# L1Demoscene_v2.net
KiCad netlist of a schematic drawn in EAGLE
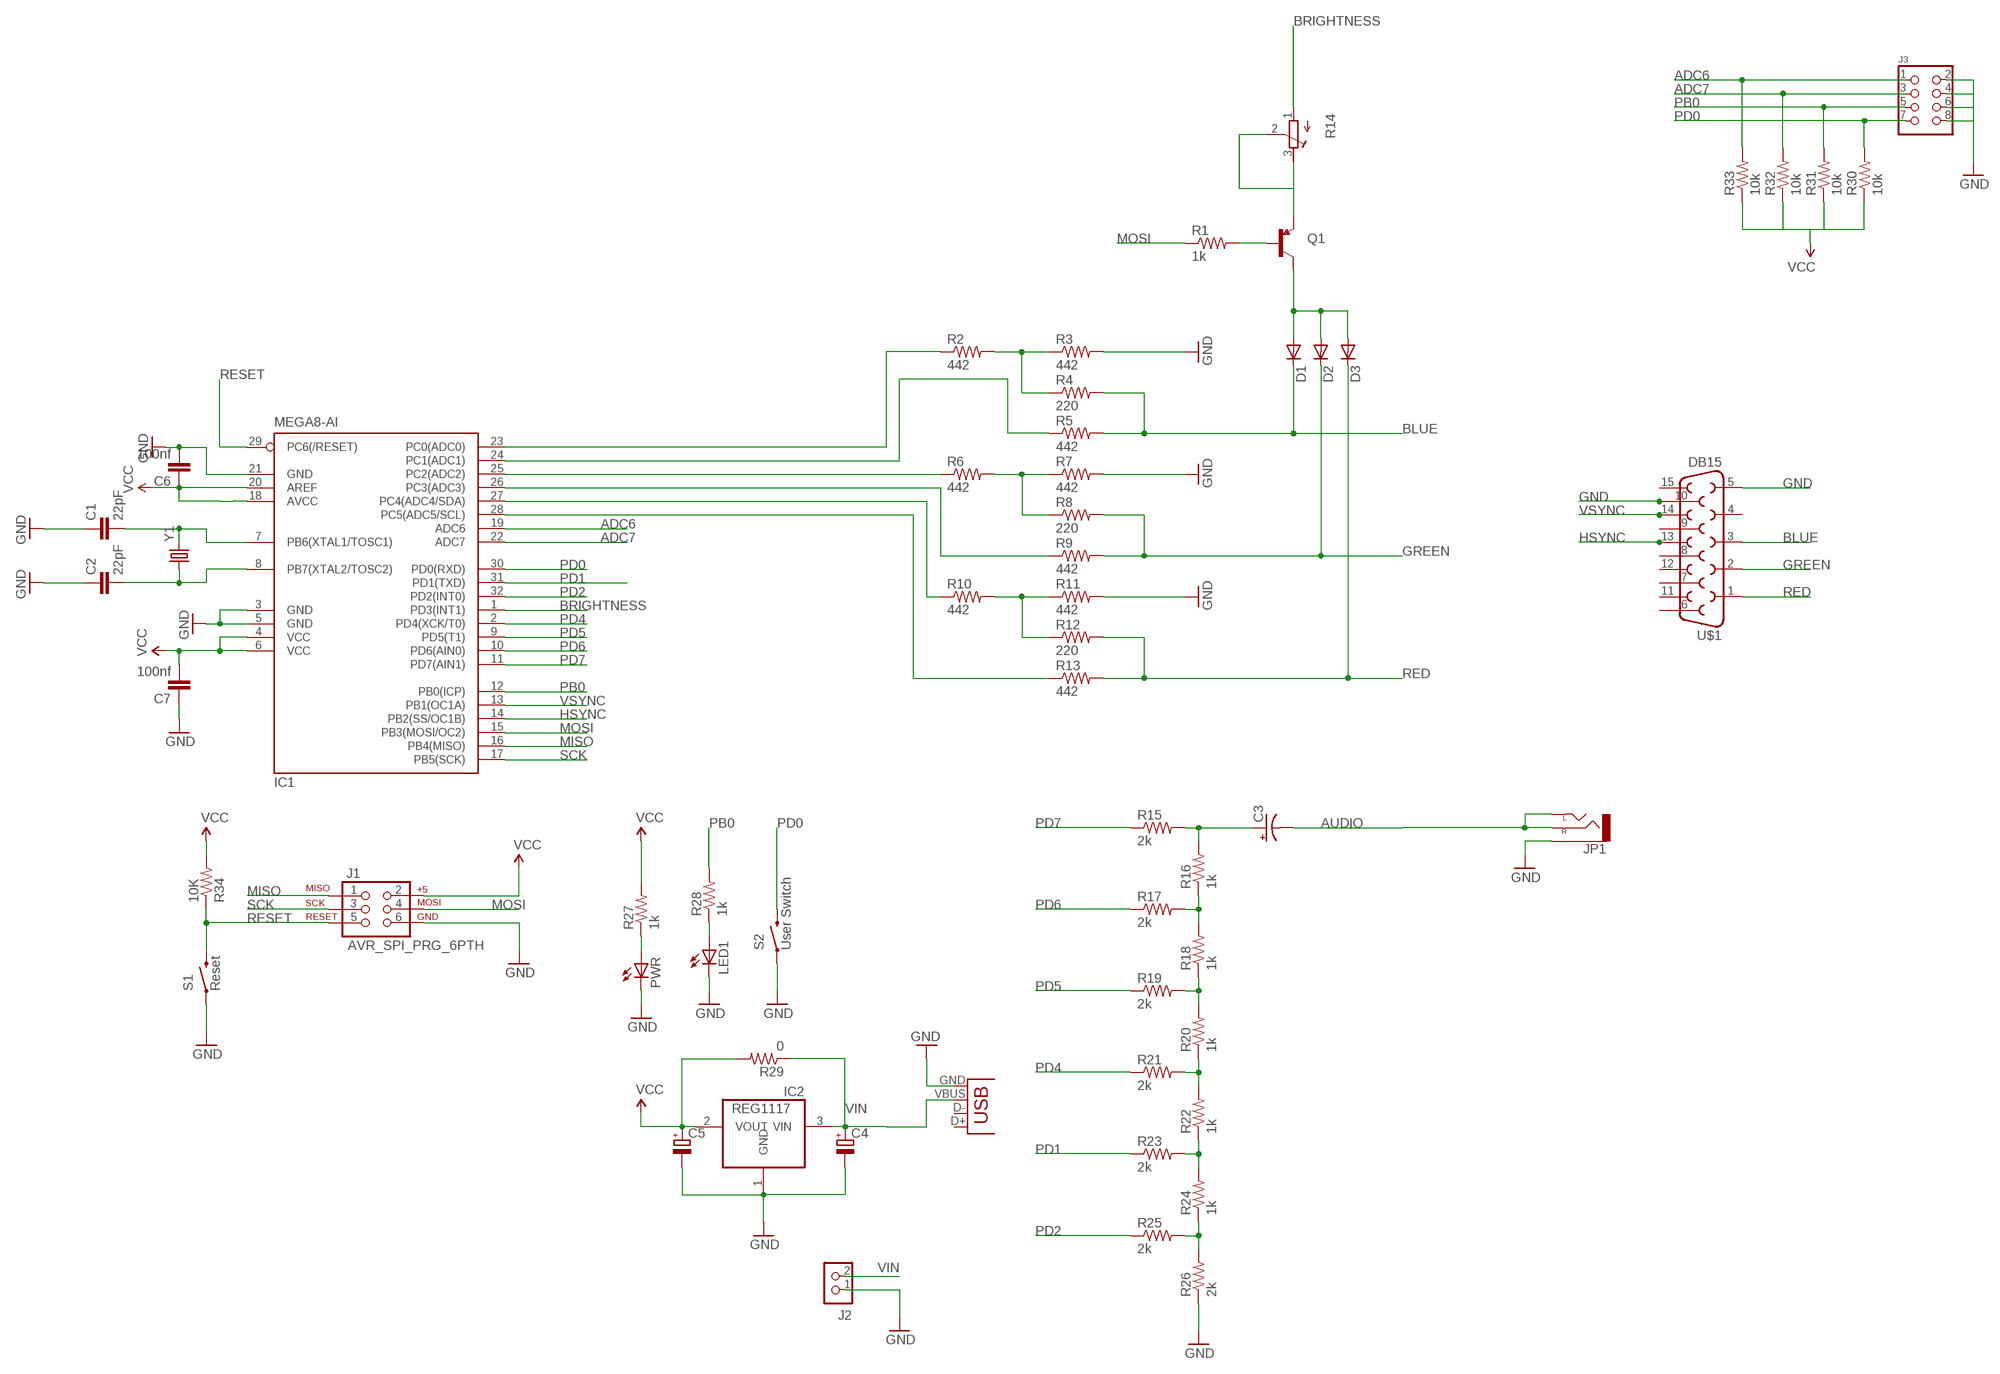
[diagram p0: schematic, sheet 1]

(export (version "E")
  (design (tool "Eeschema 10.0.6"))
  (components
    (comp (ref "10K")
      (value "R34")
      (footprint "eagle-import:0603-RES")
      (libsource (lib "eagle-import") (part "RESISTOR0603-RES"))
    )
    (comp (ref "C1")
      (value "22pF")
      (footprint "eagle-import:0603-CAP")
      (libsource (lib "eagle-import") (part "CAP0603-CAP"))
    )
    (comp (ref "C2")
      (value "22pF")
      (footprint "eagle-import:0603-CAP")
      (libsource (lib "eagle-import") (part "CAP0603-CAP"))
    )
    (comp (ref "C3")
      (value "CAP_POL1206")
      (footprint "eagle-import:EIA3216")
      (libsource (lib "eagle-import") (part "CAP_POL1206"))
    )
    (comp (ref "C4")
      (value "CAPACITOR_POL-SMC_A")
      (footprint "eagle-import:SMC_A")
      (libsource (lib "eagle-import") (part "CAPACITOR_POL-SMC_A"))
    )
    (comp (ref "C5")
      (value "CAPACITOR_POL-SMC_A")
      (footprint "eagle-import:SMC_A")
      (libsource (lib "eagle-import") (part "CAPACITOR_POL-SMC_A"))
    )
    (comp (ref "C6")
      (value "100nf")
      (footprint "eagle-import:0603-CAP")
      (libsource (lib "eagle-import") (part "CAP0603-CAP"))
    )
    (comp (ref "C7")
      (value "100nf")
      (footprint "eagle-import:0603-CAP")
      (libsource (lib "eagle-import") (part "CAP0603-CAP"))
    )
    (comp (ref "D1")
      (value "DIODESOD")
      (footprint "eagle-import:SOD-323")
      (libsource (lib "eagle-import") (part "DIODESOD"))
    )
    (comp (ref "D2")
      (value "DIODESOD")
      (footprint "eagle-import:SOD-323")
      (libsource (lib "eagle-import") (part "DIODESOD"))
    )
    (comp (ref "D3")
      (value "DIODESOD")
      (footprint "eagle-import:SOD-323")
      (libsource (lib "eagle-import") (part "DIODESOD"))
    )
    (comp (ref "IC1")
      (value "MEGA8-AI")
      (footprint "eagle-import:TQFP32-08")
      (fields (field (name "MPN") "ATMEGA8-16AU"))
      (libsource (lib "eagle-import") (part "MEGA8-AI"))
    )
    (comp (ref "IC2")
      (value "REG1117")
      (footprint "eagle-import:SOT223")
      (libsource (lib "eagle-import") (part "REG1117"))
    )
    (comp (ref "J1")
      (value "AVR_SPI_PRG_6PTH")
      (footprint "eagle-import:2X3")
      (libsource (lib "eagle-import") (part "AVR_SPI_PRG_6PTH"))
    )
    (comp (ref "J2")
      (value "CON_HEADER_1X02-PTH")
      (footprint "eagle-import:M1X2")
      (libsource (lib "eagle-import") (part "CON_HEADER_1X02-PTH"))
    )
    (comp (ref "J3")
      (value "CON_HEADER_2X04-PTH")
      (footprint "eagle-import:M2X4")
      (libsource (lib "eagle-import") (part "CON_HEADER_2X04-PTH"))
    )
    (comp (ref "JP1")
      (value "AUDIO-JACKPTH")
      (footprint "eagle-import:AUDIO-JACK")
      (libsource (lib "eagle-import") (part "AUDIO-JACKPTH"))
    )
    (comp (ref "LED1")
      (value "LED-0603")
      (footprint "eagle-import:LED-603")
      (libsource (lib "eagle-import") (part "LED-0603"))
    )
    (comp (ref "PWR")
      (value "LED-0603")
      (footprint "eagle-import:LED-603")
      (libsource (lib "eagle-import") (part "LED-0603"))
    )
    (comp (ref "Q1")
      (value "TRANSISTOR_PNPSMD")
      (footprint "eagle-import:SOT23-3")
      (libsource (lib "eagle-import") (part "TRANSISTOR_PNPSMD"))
    )
    (comp (ref "R1")
      (value "1k")
      (footprint "eagle-import:0603-RES")
      (libsource (lib "eagle-import") (part "RESISTOR0603-RES"))
    )
    (comp (ref "R2")
      (value "442")
      (footprint "eagle-import:0603-RES")
      (libsource (lib "eagle-import") (part "RESISTOR0603-RES"))
    )
    (comp (ref "R3")
      (value "442")
      (footprint "eagle-import:0603-RES")
      (libsource (lib "eagle-import") (part "RESISTOR0603-RES"))
    )
    (comp (ref "R4")
      (value "220")
      (footprint "eagle-import:0603-RES")
      (libsource (lib "eagle-import") (part "RESISTOR0603-RES"))
    )
    (comp (ref "R5")
      (value "442")
      (footprint "eagle-import:0603-RES")
      (libsource (lib "eagle-import") (part "RESISTOR0603-RES"))
    )
    (comp (ref "R6")
      (value "442")
      (footprint "eagle-import:0603-RES")
      (libsource (lib "eagle-import") (part "RESISTOR0603-RES"))
    )
    (comp (ref "R7")
      (value "442")
      (footprint "eagle-import:0603-RES")
      (libsource (lib "eagle-import") (part "RESISTOR0603-RES"))
    )
    (comp (ref "R8")
      (value "220")
      (footprint "eagle-import:0603-RES")
      (libsource (lib "eagle-import") (part "RESISTOR0603-RES"))
    )
    (comp (ref "R9")
      (value "442")
      (footprint "eagle-import:0603-RES")
      (libsource (lib "eagle-import") (part "RESISTOR0603-RES"))
    )
    (comp (ref "R10")
      (value "442")
      (footprint "eagle-import:0603-RES")
      (libsource (lib "eagle-import") (part "RESISTOR0603-RES"))
    )
    (comp (ref "R11")
      (value "442")
      (footprint "eagle-import:0603-RES")
      (libsource (lib "eagle-import") (part "RESISTOR0603-RES"))
    )
    (comp (ref "R12")
      (value "220")
      (footprint "eagle-import:0603-RES")
      (libsource (lib "eagle-import") (part "RESISTOR0603-RES"))
    )
    (comp (ref "R13")
      (value "442")
      (footprint "eagle-import:0603-RES")
      (libsource (lib "eagle-import") (part "RESISTOR0603-RES"))
    )
    (comp (ref "R14")
      (value "R-TRIMM3296W")
      (footprint "eagle-import:RTRIM3296W")
      (libsource (lib "eagle-import") (part "R-TRIMM3296W"))
    )
    (comp (ref "R15")
      (value "2k")
      (footprint "eagle-import:0603-RES")
      (libsource (lib "eagle-import") (part "RESISTOR0603-RES"))
    )
    (comp (ref "R16")
      (value "1k")
      (footprint "eagle-import:0603-RES")
      (libsource (lib "eagle-import") (part "RESISTOR0603-RES"))
    )
    (comp (ref "R17")
      (value "2k")
      (footprint "eagle-import:0603-RES")
      (libsource (lib "eagle-import") (part "RESISTOR0603-RES"))
    )
    (comp (ref "R18")
      (value "1k")
      (footprint "eagle-import:0603-RES")
      (libsource (lib "eagle-import") (part "RESISTOR0603-RES"))
    )
    (comp (ref "R19")
      (value "2k")
      (footprint "eagle-import:0603-RES")
      (libsource (lib "eagle-import") (part "RESISTOR0603-RES"))
    )
    (comp (ref "R20")
      (value "1k")
      (footprint "eagle-import:0603-RES")
      (libsource (lib "eagle-import") (part "RESISTOR0603-RES"))
    )
    (comp (ref "R21")
      (value "2k")
      (footprint "eagle-import:0603-RES")
      (libsource (lib "eagle-import") (part "RESISTOR0603-RES"))
    )
    (comp (ref "R22")
      (value "1k")
      (footprint "eagle-import:0603-RES")
      (libsource (lib "eagle-import") (part "RESISTOR0603-RES"))
    )
    (comp (ref "R23")
      (value "2k")
      (footprint "eagle-import:0603-RES")
      (libsource (lib "eagle-import") (part "RESISTOR0603-RES"))
    )
    (comp (ref "R24")
      (value "1k")
      (footprint "eagle-import:0603-RES")
      (libsource (lib "eagle-import") (part "RESISTOR0603-RES"))
    )
    (comp (ref "R25")
      (value "2k")
      (footprint "eagle-import:0603-RES")
      (libsource (lib "eagle-import") (part "RESISTOR0603-RES"))
    )
    (comp (ref "R26")
      (value "2k")
      (footprint "eagle-import:0603-RES")
      (libsource (lib "eagle-import") (part "RESISTOR0603-RES"))
    )
    (comp (ref "R27")
      (value "1k")
      (footprint "eagle-import:0603-RES")
      (libsource (lib "eagle-import") (part "RESISTOR0603-RES"))
    )
    (comp (ref "R28")
      (value "1k")
      (footprint "eagle-import:0603-RES")
      (libsource (lib "eagle-import") (part "RESISTOR0603-RES"))
    )
    (comp (ref "R29")
      (value "0")
      (footprint "eagle-import:1206")
      (libsource (lib "eagle-import") (part "RESISTOR1206"))
    )
    (comp (ref "R30")
      (value "10k")
      (footprint "eagle-import:0603-RES")
      (libsource (lib "eagle-import") (part "RESISTOR0603-RES"))
    )
    (comp (ref "R31")
      (value "10k")
      (footprint "eagle-import:0603-RES")
      (libsource (lib "eagle-import") (part "RESISTOR0603-RES"))
    )
    (comp (ref "R32")
      (value "10k")
      (footprint "eagle-import:0603-RES")
      (libsource (lib "eagle-import") (part "RESISTOR0603-RES"))
    )
    (comp (ref "R33")
      (value "10k")
      (footprint "eagle-import:0603-RES")
      (libsource (lib "eagle-import") (part "RESISTOR0603-RES"))
    )
    (comp (ref "S1")
      (value "Reset")
      (footprint "eagle-import:SPARKFUN-ELECTROMECHANICAL_TACTILE-SWITCH-1101NE")
      (libsource (lib "eagle-import") (part "SPARKFUN-ELECTROMECHANICAL_SWITCH-MOMENTARY-2-SMD-1101NE"))
    )
    (comp (ref "S2")
      (value "User Switch")
      (footprint "eagle-import:SPARKFUN-ELECTROMECHANICAL_TACTILE-SWITCH-1101NE")
      (libsource (lib "eagle-import") (part "SPARKFUN-ELECTROMECHANICAL_SWITCH-MOMENTARY-2-SMD-1101NE"))
    )
    (comp (ref "U$1")
      (value "DB15")
      (footprint "eagle-import:DB15")
      (libsource (lib "eagle-import") (part "DB15"))
    )
    (comp (ref "X1")
      (value "USB-MICROB")
      (footprint "eagle-import:USB-MICROB")
      (libsource (lib "eagle-import") (part "USB-MICROB"))
    )
    (comp (ref "Y1")
      (value "CRYSTALHC49US")
      (footprint "eagle-import:HC49US")
      (libsource (lib "eagle-import") (part "CRYSTALHC49US"))
    )
  )
  (nets
    (net (code "1") (name "ADC6") (class "Default")
      (node (ref "IC1") (pin "19") (pinfunction "ADC6_19") (pintype "bidirectional"))
      (node (ref "J3") (pin "1") (pinfunction "P$1_1") (pintype "passive"))
      (node (ref "R33") (pin "2") (pinfunction "2_2") (pintype "passive"))
    )
    (net (code "2") (name "ADC7") (class "Default")
      (node (ref "IC1") (pin "22") (pinfunction "ADC7_22") (pintype "bidirectional"))
      (node (ref "J3") (pin "3") (pinfunction "P$3_3") (pintype "passive"))
      (node (ref "R32") (pin "2") (pinfunction "2_2") (pintype "passive"))
    )
    (net (code "3") (name "AUDIO") (class "Default")
      (node (ref "C3") (pin "C") (pinfunction "-_C") (pintype "passive"))
      (node (ref "JP1") (pin "RING") (pinfunction "RIGHT_RING") (pintype "bidirectional"))
      (node (ref "JP1") (pin "TIP") (pinfunction "LEFT_TIP") (pintype "bidirectional"))
    )
    (net (code "4") (name "BLUE") (class "Default")
      (node (ref "D1") (pin "1") (pinfunction "C_1") (pintype "passive"))
      (node (ref "R4") (pin "2") (pinfunction "2_2") (pintype "passive"))
      (node (ref "R5") (pin "2") (pinfunction "2_2") (pintype "passive"))
      (node (ref "U$1") (pin "3") (pinfunction "3_3") (pintype "passive"))
    )
    (net (code "5") (name "BRIGHTNESS") (class "Default")
      (node (ref "IC1") (pin "1") (pinfunction "PD3(INT1)_1") (pintype "bidirectional"))
      (node (ref "R14") (pin "1") (pinfunction "A_1") (pintype "passive"))
    )
    (net (code "6") (name "GND") (class "Default")
      (node (ref "C1") (pin "1") (pinfunction "1_1") (pintype "passive"))
      (node (ref "C2") (pin "1") (pinfunction "1_1") (pintype "passive"))
      (node (ref "C4") (pin "-") (pinfunction "-_-") (pintype "passive"))
      (node (ref "C5") (pin "-") (pinfunction "-_-") (pintype "passive"))
      (node (ref "C6") (pin "2") (pinfunction "2_2") (pintype "passive"))
      (node (ref "C7") (pin "1") (pinfunction "1_1") (pintype "passive"))
      (node (ref "IC1") (pin "21") (pinfunction "GND_21") (pintype "power_in"))
      (node (ref "IC1") (pin "3") (pinfunction "GND_3") (pintype "power_in"))
      (node (ref "IC1") (pin "5") (pinfunction "GND_5") (pintype "power_in"))
      (node (ref "IC2") (pin "1") (pinfunction "GND_1") (pintype "power_in"))
      (node (ref "J1") (pin "6") (pinfunction "6_6") (pintype "passive"))
      (node (ref "J2") (pin "1") (pinfunction "1_1") (pintype "passive"))
      (node (ref "J3") (pin "2") (pinfunction "P$2_2") (pintype "passive"))
      (node (ref "J3") (pin "4") (pinfunction "P$4_4") (pintype "passive"))
      (node (ref "J3") (pin "6") (pinfunction "P$6_6") (pintype "passive"))
      (node (ref "J3") (pin "8") (pinfunction "P$8_8") (pintype "passive"))
      (node (ref "JP1") (pin "SLEEVE") (pinfunction "SLEEVE_SLEEVE") (pintype "bidirectional"))
      (node (ref "LED1") (pin "C") (pinfunction "C_C") (pintype "passive"))
      (node (ref "PWR") (pin "C") (pinfunction "C_C") (pintype "passive"))
      (node (ref "R11") (pin "2") (pinfunction "2_2") (pintype "passive"))
      (node (ref "R26") (pin "1") (pinfunction "1_1") (pintype "passive"))
      (node (ref "R3") (pin "2") (pinfunction "2_2") (pintype "passive"))
      (node (ref "R7") (pin "2") (pinfunction "2_2") (pintype "passive"))
      (node (ref "S1") (pin "P$1") (pinfunction "1_P$1") (pintype "passive"))
      (node (ref "S2") (pin "P$1") (pinfunction "1_P$1") (pintype "passive"))
      (node (ref "U$1") (pin "10") (pinfunction "10_10") (pintype "passive"))
      (node (ref "U$1") (pin "5") (pinfunction "5_5") (pintype "passive"))
      (node (ref "X1") (pin "GND") (pinfunction "GND_GND") (pintype "bidirectional"))
    )
    (net (code "7") (name "GREEN") (class "Default")
      (node (ref "D2") (pin "1") (pinfunction "C_1") (pintype "passive"))
      (node (ref "R8") (pin "2") (pinfunction "2_2") (pintype "passive"))
      (node (ref "R9") (pin "2") (pinfunction "2_2") (pintype "passive"))
      (node (ref "U$1") (pin "2") (pinfunction "2_2") (pintype "passive"))
    )
    (net (code "8") (name "HSYNC") (class "Default")
      (node (ref "IC1") (pin "14") (pinfunction "PB2(SS/OC1B)_14") (pintype "bidirectional"))
      (node (ref "U$1") (pin "13") (pinfunction "13_13") (pintype "passive"))
    )
    (net (code "9") (name "MISO") (class "Default")
      (node (ref "IC1") (pin "16") (pinfunction "PB4(MISO)_16") (pintype "bidirectional"))
      (node (ref "J1") (pin "1") (pinfunction "1_1") (pintype "passive"))
    )
    (net (code "10") (name "MOSI") (class "Default")
      (node (ref "IC1") (pin "15") (pinfunction "PB3(MOSI/OC2)_15") (pintype "bidirectional"))
      (node (ref "J1") (pin "4") (pinfunction "4_4") (pintype "passive"))
      (node (ref "R1") (pin "1") (pinfunction "1_1") (pintype "passive"))
    )
    (net (code "11") (name "Net-(C3-+)") (class "Default")
      (node (ref "C3") (pin "A") (pinfunction "+_A") (pintype "passive"))
      (node (ref "R15") (pin "2") (pinfunction "2_2") (pintype "passive"))
      (node (ref "R16") (pin "2") (pinfunction "2_2") (pintype "passive"))
    )
    (net (code "12") (name "Net-(D1-A)") (class "Default")
      (node (ref "D1") (pin "2") (pinfunction "A_2") (pintype "passive"))
      (node (ref "D2") (pin "2") (pinfunction "A_2") (pintype "passive"))
      (node (ref "D3") (pin "2") (pinfunction "A_2") (pintype "passive"))
      (node (ref "Q1") (pin "3") (pinfunction "C_3") (pintype "passive"))
    )
    (net (code "13") (name "Net-(IC1-PB6(XTAL1{slash}TOSC1))") (class "Default")
      (node (ref "C1") (pin "2") (pinfunction "2_2") (pintype "passive"))
      (node (ref "IC1") (pin "7") (pinfunction "PB6(XTAL1/TOSC1)_7") (pintype "bidirectional"))
      (node (ref "Y1") (pin "2") (pinfunction "2_2") (pintype "passive"))
    )
    (net (code "14") (name "Net-(IC1-PB7(XTAL2{slash}TOSC2))") (class "Default")
      (node (ref "C2") (pin "2") (pinfunction "2_2") (pintype "passive"))
      (node (ref "IC1") (pin "8") (pinfunction "PB7(XTAL2/TOSC2)_8") (pintype "bidirectional"))
      (node (ref "Y1") (pin "1") (pinfunction "1_1") (pintype "passive"))
    )
    (net (code "15") (name "Net-(IC1-PC0(ADC0))") (class "Default")
      (node (ref "IC1") (pin "23") (pinfunction "PC0(ADC0)_23") (pintype "bidirectional"))
      (node (ref "R2") (pin "1") (pinfunction "1_1") (pintype "passive"))
    )
    (net (code "16") (name "Net-(IC1-PC1(ADC1))") (class "Default")
      (node (ref "IC1") (pin "24") (pinfunction "PC1(ADC1)_24") (pintype "bidirectional"))
      (node (ref "R5") (pin "1") (pinfunction "1_1") (pintype "passive"))
    )
    (net (code "17") (name "Net-(IC1-PC2(ADC2))") (class "Default")
      (node (ref "IC1") (pin "25") (pinfunction "PC2(ADC2)_25") (pintype "bidirectional"))
      (node (ref "R6") (pin "1") (pinfunction "1_1") (pintype "passive"))
    )
    (net (code "18") (name "Net-(IC1-PC3(ADC3))") (class "Default")
      (node (ref "IC1") (pin "26") (pinfunction "PC3(ADC3)_26") (pintype "bidirectional"))
      (node (ref "R9") (pin "1") (pinfunction "1_1") (pintype "passive"))
    )
    (net (code "19") (name "Net-(IC1-PC4(ADC4{slash}SDA))") (class "Default")
      (node (ref "IC1") (pin "27") (pinfunction "PC4(ADC4/SDA)_27") (pintype "bidirectional"))
      (node (ref "R10") (pin "1") (pinfunction "1_1") (pintype "passive"))
    )
    (net (code "20") (name "Net-(IC1-PC5(ADC5{slash}SCL))") (class "Default")
      (node (ref "IC1") (pin "28") (pinfunction "PC5(ADC5/SCL)_28") (pintype "bidirectional"))
      (node (ref "R13") (pin "1") (pinfunction "1_1") (pintype "passive"))
    )
    (net (code "21") (name "Net-(LED1-PadA)") (class "Default")
      (node (ref "LED1") (pin "A") (pinfunction "A_A") (pintype "passive"))
      (node (ref "R28") (pin "1") (pinfunction "1_1") (pintype "passive"))
    )
    (net (code "22") (name "Net-(PWR-PadA)") (class "Default")
      (node (ref "PWR") (pin "A") (pinfunction "A_A") (pintype "passive"))
      (node (ref "R27") (pin "1") (pinfunction "1_1") (pintype "passive"))
    )
    (net (code "23") (name "Net-(Q1-B)") (class "Default")
      (node (ref "Q1") (pin "1") (pinfunction "B_1") (pintype "passive"))
      (node (ref "R1") (pin "2") (pinfunction "2_2") (pintype "passive"))
    )
    (net (code "24") (name "Net-(Q1-E)") (class "Default")
      (node (ref "Q1") (pin "2") (pinfunction "E_2") (pintype "passive"))
      (node (ref "R14") (pin "2") (pinfunction "S_2") (pintype "passive"))
      (node (ref "R14") (pin "3") (pinfunction "E_3") (pintype "passive"))
    )
    (net (code "25") (name "Net-(R2-Pad2)") (class "Default")
      (node (ref "R2") (pin "2") (pinfunction "2_2") (pintype "passive"))
      (node (ref "R3") (pin "1") (pinfunction "1_1") (pintype "passive"))
      (node (ref "R4") (pin "1") (pinfunction "1_1") (pintype "passive"))
    )
    (net (code "26") (name "Net-(R6-Pad2)") (class "Default")
      (node (ref "R6") (pin "2") (pinfunction "2_2") (pintype "passive"))
      (node (ref "R7") (pin "1") (pinfunction "1_1") (pintype "passive"))
      (node (ref "R8") (pin "1") (pinfunction "1_1") (pintype "passive"))
    )
    (net (code "27") (name "Net-(R10-Pad2)") (class "Default")
      (node (ref "R10") (pin "2") (pinfunction "2_2") (pintype "passive"))
      (node (ref "R11") (pin "1") (pinfunction "1_1") (pintype "passive"))
      (node (ref "R12") (pin "1") (pinfunction "1_1") (pintype "passive"))
    )
    (net (code "28") (name "Net-(R16-Pad1)") (class "Default")
      (node (ref "R16") (pin "1") (pinfunction "1_1") (pintype "passive"))
      (node (ref "R17") (pin "2") (pinfunction "2_2") (pintype "passive"))
      (node (ref "R18") (pin "2") (pinfunction "2_2") (pintype "passive"))
    )
    (net (code "29") (name "Net-(R18-Pad1)") (class "Default")
      (node (ref "R18") (pin "1") (pinfunction "1_1") (pintype "passive"))
      (node (ref "R19") (pin "2") (pinfunction "2_2") (pintype "passive"))
      (node (ref "R20") (pin "2") (pinfunction "2_2") (pintype "passive"))
    )
    (net (code "30") (name "Net-(R20-Pad1)") (class "Default")
      (node (ref "R20") (pin "1") (pinfunction "1_1") (pintype "passive"))
      (node (ref "R21") (pin "2") (pinfunction "2_2") (pintype "passive"))
      (node (ref "R22") (pin "2") (pinfunction "2_2") (pintype "passive"))
    )
    (net (code "31") (name "Net-(R22-Pad1)") (class "Default")
      (node (ref "R22") (pin "1") (pinfunction "1_1") (pintype "passive"))
      (node (ref "R23") (pin "2") (pinfunction "2_2") (pintype "passive"))
      (node (ref "R24") (pin "2") (pinfunction "2_2") (pintype "passive"))
    )
    (net (code "32") (name "Net-(R24-Pad1)") (class "Default")
      (node (ref "R24") (pin "1") (pinfunction "1_1") (pintype "passive"))
      (node (ref "R25") (pin "2") (pinfunction "2_2") (pintype "passive"))
      (node (ref "R26") (pin "2") (pinfunction "2_2") (pintype "passive"))
    )
    (net (code "33") (name "PB0") (class "Default")
      (node (ref "IC1") (pin "12") (pinfunction "PB0(ICP)_12") (pintype "bidirectional"))
      (node (ref "J3") (pin "5") (pinfunction "P$5_5") (pintype "passive"))
      (node (ref "R28") (pin "2") (pinfunction "2_2") (pintype "passive"))
      (node (ref "R31") (pin "2") (pinfunction "2_2") (pintype "passive"))
    )
    (net (code "34") (name "PD0") (class "Default")
      (node (ref "IC1") (pin "30") (pinfunction "PD0(RXD)_30") (pintype "bidirectional"))
      (node (ref "J3") (pin "7") (pinfunction "P$7_7") (pintype "passive"))
      (node (ref "R30") (pin "2") (pinfunction "2_2") (pintype "passive"))
      (node (ref "S2") (pin "P$2") (pinfunction "2_P$2") (pintype "passive"))
    )
    (net (code "35") (name "PD1") (class "Default")
      (node (ref "IC1") (pin "31") (pinfunction "PD1(TXD)_31") (pintype "bidirectional"))
      (node (ref "R23") (pin "1") (pinfunction "1_1") (pintype "passive"))
    )
    (net (code "36") (name "PD2") (class "Default")
      (node (ref "IC1") (pin "32") (pinfunction "PD2(INT0)_32") (pintype "bidirectional"))
      (node (ref "R25") (pin "1") (pinfunction "1_1") (pintype "passive"))
    )
    (net (code "37") (name "PD4") (class "Default")
      (node (ref "IC1") (pin "2") (pinfunction "PD4(XCK/T0)_2") (pintype "bidirectional"))
      (node (ref "R21") (pin "1") (pinfunction "1_1") (pintype "passive"))
    )
    (net (code "38") (name "PD5") (class "Default")
      (node (ref "IC1") (pin "9") (pinfunction "PD5(T1)_9") (pintype "bidirectional"))
      (node (ref "R19") (pin "1") (pinfunction "1_1") (pintype "passive"))
    )
    (net (code "39") (name "PD6") (class "Default")
      (node (ref "IC1") (pin "10") (pinfunction "PD6(AIN0)_10") (pintype "bidirectional"))
      (node (ref "R17") (pin "1") (pinfunction "1_1") (pintype "passive"))
    )
    (net (code "40") (name "PD7") (class "Default")
      (node (ref "IC1") (pin "11") (pinfunction "PD7(AIN1)_11") (pintype "bidirectional"))
      (node (ref "R15") (pin "1") (pinfunction "1_1") (pintype "passive"))
    )
    (net (code "41") (name "RED") (class "Default")
      (node (ref "D3") (pin "1") (pinfunction "C_1") (pintype "passive"))
      (node (ref "R12") (pin "2") (pinfunction "2_2") (pintype "passive"))
      (node (ref "R13") (pin "2") (pinfunction "2_2") (pintype "passive"))
      (node (ref "U$1") (pin "1") (pinfunction "1_1") (pintype "passive"))
    )
    (net (code "42") (name "RESET") (class "Default")
      (node (ref "10K") (pin "1") (pinfunction "1_1") (pintype "passive"))
      (node (ref "IC1") (pin "29") (pinfunction "PC6(/RESET)_29") (pintype "bidirectional"))
      (node (ref "J1") (pin "5") (pinfunction "5_5") (pintype "passive"))
      (node (ref "S1") (pin "P$2") (pinfunction "2_P$2") (pintype "passive"))
    )
    (net (code "43") (name "SCK") (class "Default")
      (node (ref "IC1") (pin "17") (pinfunction "PB5(SCK)_17") (pintype "bidirectional"))
      (node (ref "J1") (pin "3") (pinfunction "3_3") (pintype "passive"))
    )
    (net (code "44") (name "VCC") (class "Default")
      (node (ref "10K") (pin "2") (pinfunction "2_2") (pintype "passive"))
      (node (ref "C5") (pin "+") (pinfunction "+_+") (pintype "passive"))
      (node (ref "C6") (pin "1") (pinfunction "1_1") (pintype "passive"))
      (node (ref "C7") (pin "2") (pinfunction "2_2") (pintype "passive"))
      (node (ref "IC1") (pin "18") (pinfunction "AVCC_18") (pintype "power_in"))
      (node (ref "IC1") (pin "20") (pinfunction "AREF_20") (pintype "passive"))
      (node (ref "IC1") (pin "4") (pinfunction "VCC_4") (pintype "power_in"))
      (node (ref "IC1") (pin "6") (pinfunction "VCC_6") (pintype "power_in"))
      (node (ref "IC2") (pin "2") (pinfunction "VOUT_2") (pintype "output"))
      (node (ref "J1") (pin "2") (pinfunction "2_2") (pintype "passive"))
      (node (ref "R27") (pin "2") (pinfunction "2_2") (pintype "passive"))
      (node (ref "R29") (pin "2") (pinfunction "2_2") (pintype "passive"))
      (node (ref "R30") (pin "1") (pinfunction "1_1") (pintype "passive"))
      (node (ref "R31") (pin "1") (pinfunction "1_1") (pintype "passive"))
      (node (ref "R32") (pin "1") (pinfunction "1_1") (pintype "passive"))
      (node (ref "R33") (pin "1") (pinfunction "1_1") (pintype "passive"))
    )
    (net (code "45") (name "VIN") (class "Default")
      (node (ref "C4") (pin "+") (pinfunction "+_+") (pintype "passive"))
      (node (ref "IC2") (pin "3") (pinfunction "VIN_3") (pintype "input"))
      (node (ref "J2") (pin "2") (pinfunction "2_2") (pintype "passive"))
      (node (ref "R29") (pin "1") (pinfunction "1_1") (pintype "passive"))
      (node (ref "X1") (pin "VBUS") (pinfunction "VBUS_VBUS") (pintype "bidirectional"))
    )
    (net (code "46") (name "VSYNC") (class "Default")
      (node (ref "IC1") (pin "13") (pinfunction "PB1(OC1A)_13") (pintype "bidirectional"))
      (node (ref "U$1") (pin "14") (pinfunction "14_14") (pintype "passive"))
    )
    (net (code "47") (name "unconnected-(U$1-Pad4)") (class "Default")
      (node (ref "U$1") (pin "4") (pinfunction "4_4") (pintype "passive"))
    )
    (net (code "48") (name "unconnected-(U$1-Pad6)") (class "Default")
      (node (ref "U$1") (pin "6") (pinfunction "6_6") (pintype "passive"))
    )
    (net (code "49") (name "unconnected-(U$1-Pad7)") (class "Default")
      (node (ref "U$1") (pin "7") (pinfunction "7_7") (pintype "passive"))
    )
    (net (code "50") (name "unconnected-(U$1-Pad8)") (class "Default")
      (node (ref "U$1") (pin "8") (pinfunction "8_8") (pintype "passive"))
    )
    (net (code "51") (name "unconnected-(U$1-Pad9)") (class "Default")
      (node (ref "U$1") (pin "9") (pinfunction "9_9") (pintype "passive"))
    )
    (net (code "52") (name "unconnected-(U$1-Pad11)") (class "Default")
      (node (ref "U$1") (pin "11") (pinfunction "11_11") (pintype "passive"))
    )
    (net (code "53") (name "unconnected-(U$1-Pad12)") (class "Default")
      (node (ref "U$1") (pin "12") (pinfunction "12_12") (pintype "passive"))
    )
    (net (code "54") (name "unconnected-(U$1-Pad15)") (class "Default")
      (node (ref "U$1") (pin "15") (pinfunction "15_15") (pintype "passive"))
    )
    (net (code "55") (name "unconnected-(X1-PadD+)") (class "Default")
      (node (ref "X1") (pin "D+") (pinfunction "D+_D+") (pintype "bidirectional"))
    )
    (net (code "56") (name "unconnected-(X1-PadD-)") (class "Default")
      (node (ref "X1") (pin "D-") (pinfunction "D-_D-") (pintype "bidirectional"))
    )
  )
)
